# PCIe_ETHERNET.net
KiCad netlist of a schematic drawn in Altium Designer
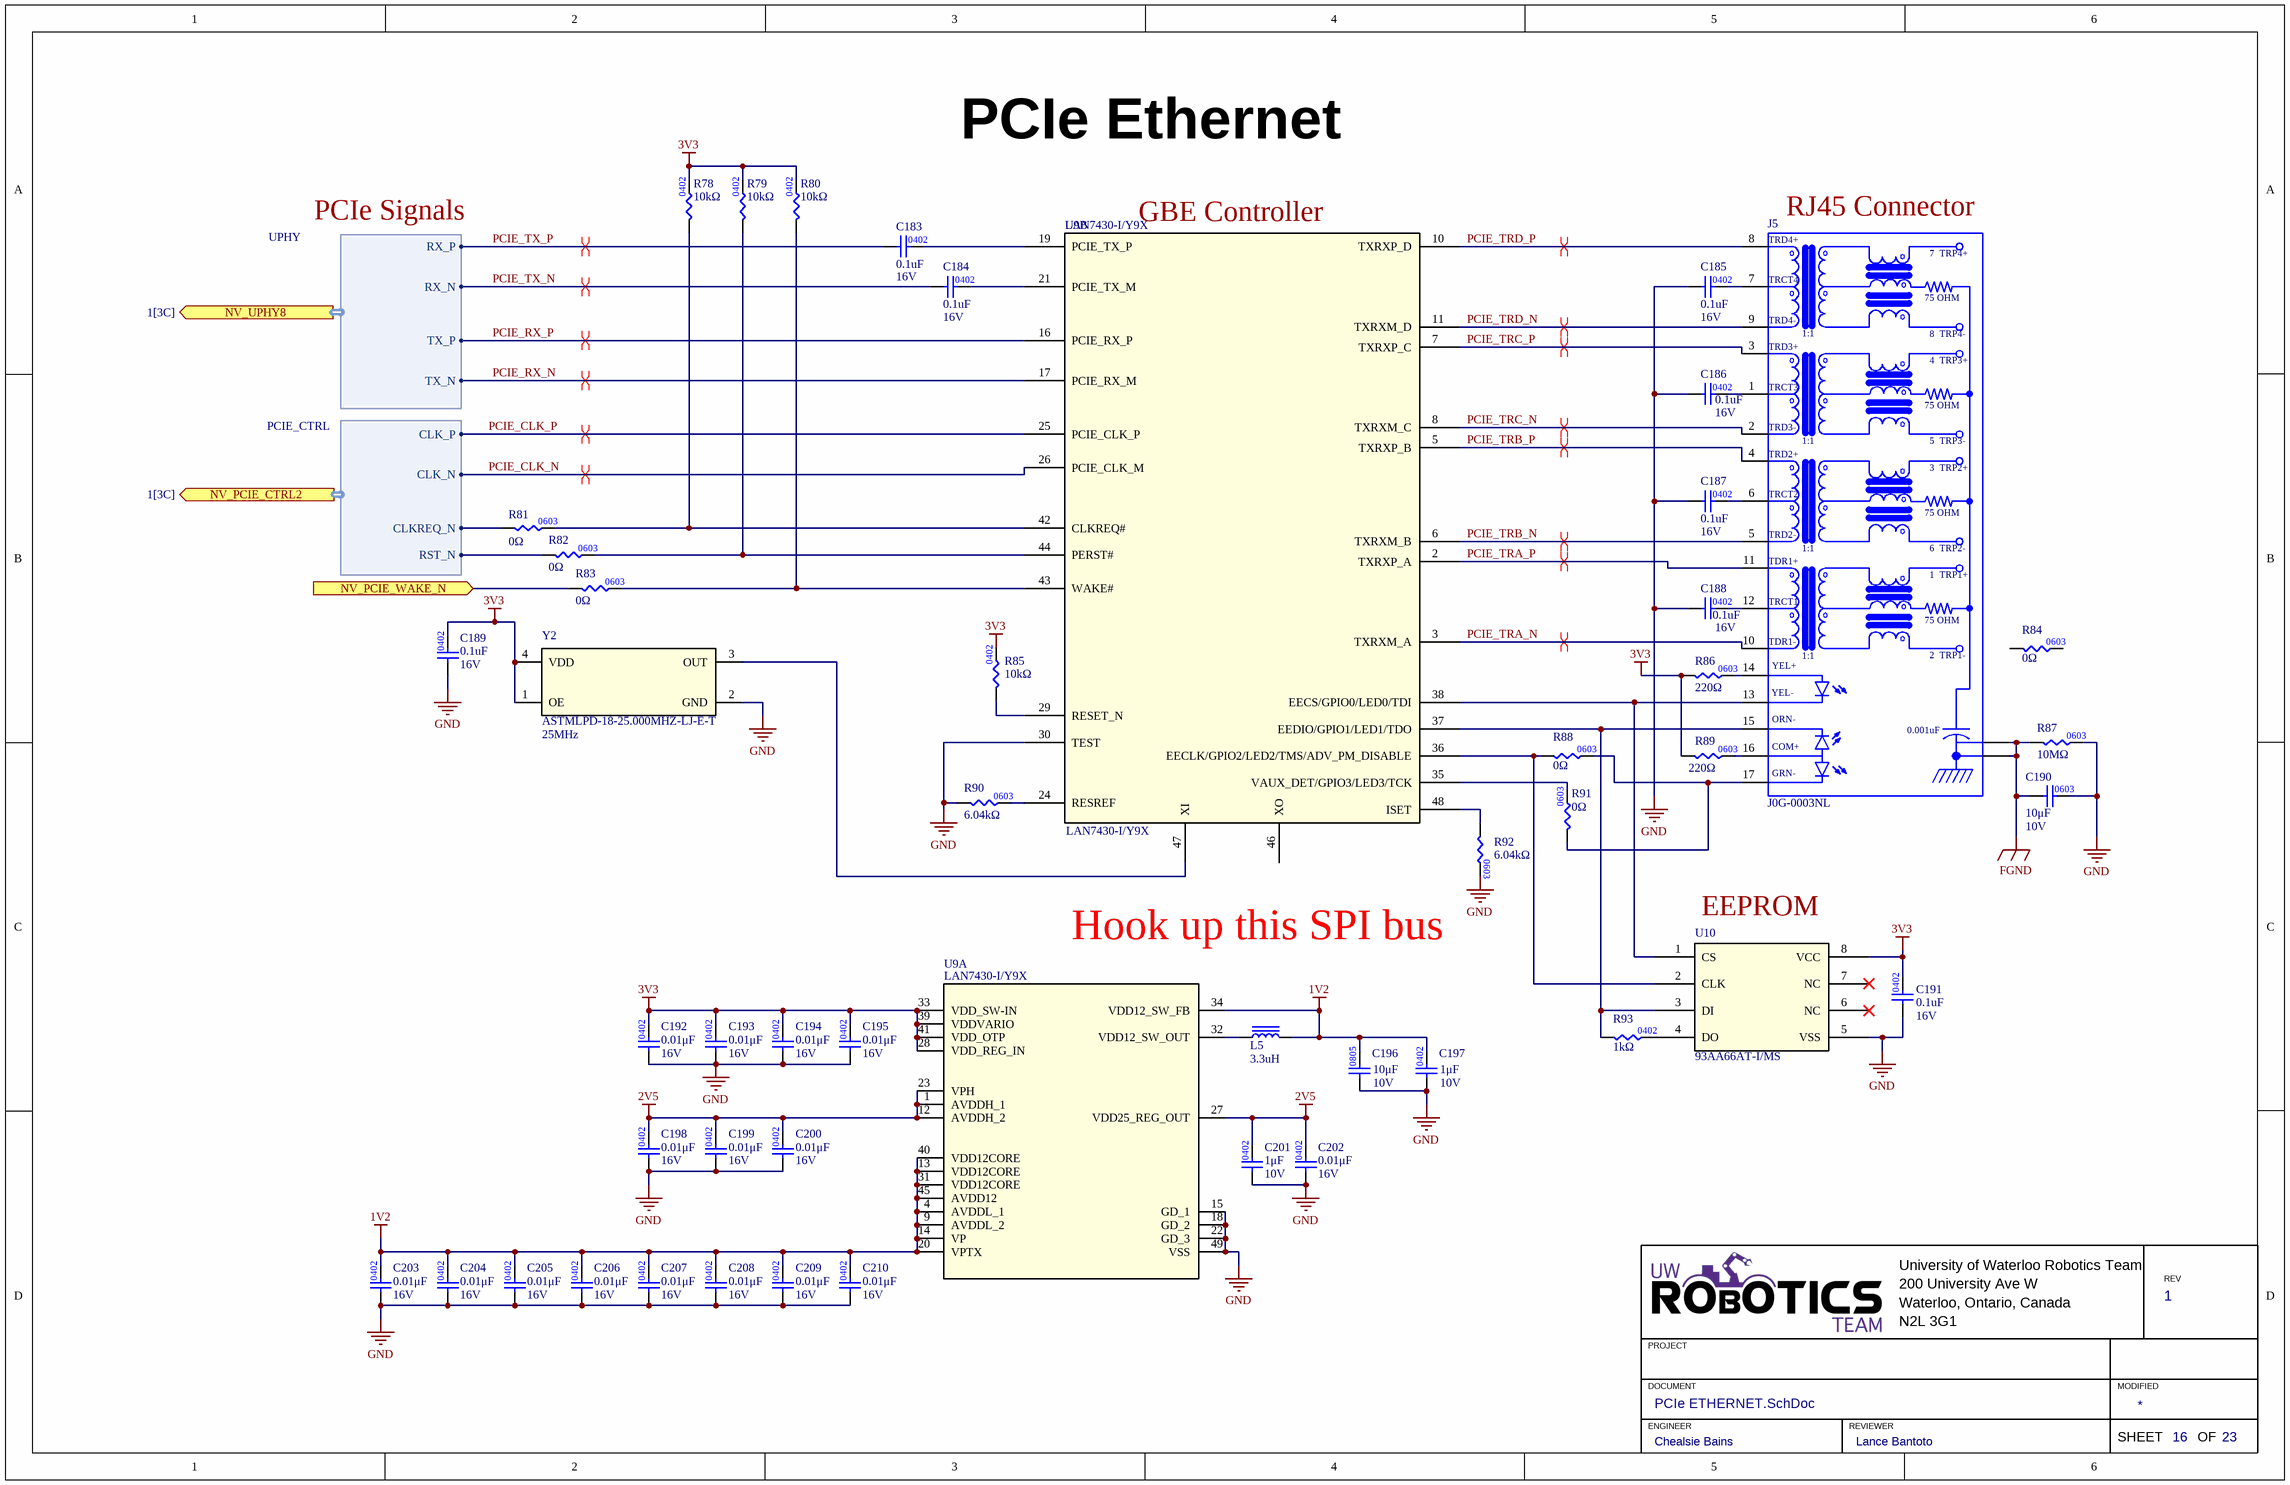
[diagram p0: PCIe ETHERNET.SchDoc]

(export (version "E")
  (design (tool "Eeschema 10.0.6"))
  (components
    (comp (ref "C183")
      (value "CAP_0.1uF_16V_X7R_0402")
      (footprint "CAP0402")
      (description "CAP CER 0.1UF 16V X7R 0402")
      (fields (field (name "CAPACITANCE") "0.1uF") (field (name "VOLTAGE RATING") "16V"))
      (libsource (lib "UWRT_Schematic_Library_2020") (part "CAP_0.1uF_16V_X7R_0402"))
    )
    (comp (ref "C184")
      (value "CAP_0.1uF_16V_X7R_0402")
      (footprint "CAP0402")
      (description "CAP CER 0.1UF 16V X7R 0402")
      (fields (field (name "CAPACITANCE") "0.1uF") (field (name "VOLTAGE RATING") "16V"))
      (libsource (lib "UWRT_Schematic_Library_2020") (part "CAP_0.1uF_16V_X7R_0402"))
    )
    (comp (ref "C185")
      (value "CAP_0.1uF_16V_X7R_0402")
      (footprint "CAP0402")
      (description "CAP CER 0.1UF 16V X7R 0402")
      (fields (field (name "CAPACITANCE") "0.1uF") (field (name "VOLTAGE RATING") "16V"))
      (libsource (lib "UWRT_Schematic_Library_2020") (part "CAP_0.1uF_16V_X7R_0402"))
    )
    (comp (ref "C186")
      (value "CAP_0.1uF_16V_X7R_0402")
      (footprint "CAP0402")
      (description "CAP CER 0.1UF 16V X7R 0402")
      (fields (field (name "CAPACITANCE") "0.1uF") (field (name "VOLTAGE RATING") "16V"))
      (libsource (lib "UWRT_Schematic_Library_2020") (part "CAP_0.1uF_16V_X7R_0402"))
    )
    (comp (ref "C187")
      (value "CAP_0.1uF_16V_X7R_0402")
      (footprint "CAP0402")
      (description "CAP CER 0.1UF 16V X7R 0402")
      (fields (field (name "CAPACITANCE") "0.1uF") (field (name "VOLTAGE RATING") "16V"))
      (libsource (lib "UWRT_Schematic_Library_2020") (part "CAP_0.1uF_16V_X7R_0402"))
    )
    (comp (ref "C188")
      (value "CAP_0.1uF_16V_X7R_0402")
      (footprint "CAP0402")
      (description "CAP CER 0.1UF 16V X7R 0402")
      (fields (field (name "CAPACITANCE") "0.1uF") (field (name "VOLTAGE RATING") "16V"))
      (libsource (lib "UWRT_Schematic_Library_2020") (part "CAP_0.1uF_16V_X7R_0402"))
    )
    (comp (ref "C189")
      (value "CAP_0.1uF_16V_X7R_0402")
      (footprint "CAP0402")
      (description "CAP CER 0.1UF 16V X7R 0402")
      (fields (field (name "CAPACITANCE") "0.1uF") (field (name "VOLTAGE RATING") "16V"))
      (libsource (lib "UWRT_Schematic_Library_2020") (part "CAP_0.1uF_16V_X7R_0402"))
    )
    (comp (ref "C190")
      (value "10μF")
      (footprint "CAP0603")
      (description "CAP CER 10UF 10V X5R 0603")
      (fields (field (name "VOLTAGE RATING") "10V") (field (name "Comment") "CAP_10uF_10V_0603"))
      (libsource (lib "UWRT_Schematic_Library_2020") (part "CAP_10uF_10V_0603"))
    )
    (comp (ref "C191")
      (value "CAP_0.1uF_16V_X7R_0402")
      (footprint "CAP0402")
      (description "CAP CER 0.1UF 16V X7R 0402")
      (fields (field (name "CAPACITANCE") "0.1uF") (field (name "VOLTAGE RATING") "16V"))
      (libsource (lib "UWRT_Schematic_Library_2020") (part "CAP_0.1uF_16V_X7R_0402"))
    )
    (comp (ref "C192")
      (value "CAP_0.01uF_16V_X7R_0402")
      (footprint "CAP0402")
      (description "CAP CER 0.01uF 16V X7R 0402")
      (fields
        (field (name "MANUFACTURER") "KEMET")
        (field (name "MANUFACTURER PART NUMBER") "C0402C103J4RACTU")
        (field (name "CAPACITANCE") "0.01μF")
        (field (name "VOLTAGE RATING") "16V")
      )
      (libsource (lib "UWRT_Schematic_Library_2020") (part "CAP_0.01uF_16V_X7R_0402"))
    )
    (comp (ref "C193")
      (value "CAP_0.01uF_16V_X7R_0402")
      (footprint "CAP0402")
      (description "CAP CER 0.01uF 16V X7R 0402")
      (fields
        (field (name "MANUFACTURER") "KEMET")
        (field (name "MANUFACTURER PART NUMBER") "C0402C103J4RACTU")
        (field (name "CAPACITANCE") "0.01μF")
        (field (name "VOLTAGE RATING") "16V")
      )
      (libsource (lib "UWRT_Schematic_Library_2020") (part "CAP_0.01uF_16V_X7R_0402"))
    )
    (comp (ref "C194")
      (value "CAP_0.01uF_16V_X7R_0402")
      (footprint "CAP0402")
      (description "CAP CER 0.01uF 16V X7R 0402")
      (fields
        (field (name "MANUFACTURER") "KEMET")
        (field (name "MANUFACTURER PART NUMBER") "C0402C103J4RACTU")
        (field (name "CAPACITANCE") "0.01μF")
        (field (name "VOLTAGE RATING") "16V")
      )
      (libsource (lib "UWRT_Schematic_Library_2020") (part "CAP_0.01uF_16V_X7R_0402"))
    )
    (comp (ref "C195")
      (value "CAP_0.01uF_16V_X7R_0402")
      (footprint "CAP0402")
      (description "CAP CER 0.01uF 16V X7R 0402")
      (fields
        (field (name "MANUFACTURER") "KEMET")
        (field (name "MANUFACTURER PART NUMBER") "C0402C103J4RACTU")
        (field (name "CAPACITANCE") "0.01μF")
        (field (name "VOLTAGE RATING") "16V")
      )
      (libsource (lib "UWRT_Schematic_Library_2020") (part "CAP_0.01uF_16V_X7R_0402"))
    )
    (comp (ref "C196")
      (value "10μF")
      (footprint "CAP0805")
      (description "CAP CER 10UF 10V X6S 0805")
      (fields (field (name "VOLTAGE RATING") "10V") (field (name "Comment") "CAP_10UF_10V_X6S_0805"))
      (libsource (lib "UWRT_Schematic_Library_2020") (part "CAP_10UF_10V_X6S_0805"))
    )
    (comp (ref "C197")
      (value "CAP_1UF_10V_0402_X5R")
      (footprint "CAP0402")
      (description "CAP CER 1UF 10V X5R 0402")
      (fields
        (field (name "MANUFACTURER") "Kyocera AVX")
        (field (name "MANUFACTURER PART NUMBER") "0402ZD105MAT2A")
        (field (name "CAPACITANCE") "1μF")
        (field (name "RATED DC VOLTAGE (URDC)") "10V")
      )
      (libsource (lib "UWRT_Schematic_Library_2020") (part "CAP_1UF_10V_0402_X5R"))
    )
    (comp (ref "C198")
      (value "CAP_0.01uF_16V_X7R_0402")
      (footprint "CAP0402")
      (description "CAP CER 0.01uF 16V X7R 0402")
      (fields
        (field (name "MANUFACTURER") "KEMET")
        (field (name "MANUFACTURER PART NUMBER") "C0402C103J4RACTU")
        (field (name "CAPACITANCE") "0.01μF")
        (field (name "VOLTAGE RATING") "16V")
      )
      (libsource (lib "UWRT_Schematic_Library_2020") (part "CAP_0.01uF_16V_X7R_0402"))
    )
    (comp (ref "C199")
      (value "CAP_0.01uF_16V_X7R_0402")
      (footprint "CAP0402")
      (description "CAP CER 0.01uF 16V X7R 0402")
      (fields
        (field (name "MANUFACTURER") "KEMET")
        (field (name "MANUFACTURER PART NUMBER") "C0402C103J4RACTU")
        (field (name "CAPACITANCE") "0.01μF")
        (field (name "VOLTAGE RATING") "16V")
      )
      (libsource (lib "UWRT_Schematic_Library_2020") (part "CAP_0.01uF_16V_X7R_0402"))
    )
    (comp (ref "C200")
      (value "CAP_0.01uF_16V_X7R_0402")
      (footprint "CAP0402")
      (description "CAP CER 0.01uF 16V X7R 0402")
      (fields
        (field (name "MANUFACTURER") "KEMET")
        (field (name "MANUFACTURER PART NUMBER") "C0402C103J4RACTU")
        (field (name "CAPACITANCE") "0.01μF")
        (field (name "VOLTAGE RATING") "16V")
      )
      (libsource (lib "UWRT_Schematic_Library_2020") (part "CAP_0.01uF_16V_X7R_0402"))
    )
    (comp (ref "C201")
      (value "CAP_1UF_10V_0402_X5R")
      (footprint "CAP0402")
      (description "CAP CER 1UF 10V X5R 0402")
      (fields
        (field (name "MANUFACTURER") "Kyocera AVX")
        (field (name "MANUFACTURER PART NUMBER") "0402ZD105MAT2A")
        (field (name "CAPACITANCE") "1μF")
        (field (name "RATED DC VOLTAGE (URDC)") "10V")
      )
      (libsource (lib "UWRT_Schematic_Library_2020") (part "CAP_1UF_10V_0402_X5R"))
    )
    (comp (ref "C202")
      (value "CAP_0.01uF_16V_X7R_0402")
      (footprint "CAP0402")
      (description "CAP CER 0.01uF 16V X7R 0402")
      (fields
        (field (name "MANUFACTURER") "KEMET")
        (field (name "MANUFACTURER PART NUMBER") "C0402C103J4RACTU")
        (field (name "CAPACITANCE") "0.01μF")
        (field (name "VOLTAGE RATING") "16V")
      )
      (libsource (lib "UWRT_Schematic_Library_2020") (part "CAP_0.01uF_16V_X7R_0402"))
    )
    (comp (ref "C203")
      (value "CAP_0.01uF_16V_X7R_0402")
      (footprint "CAP0402")
      (description "CAP CER 0.01uF 16V X7R 0402")
      (fields
        (field (name "MANUFACTURER") "KEMET")
        (field (name "MANUFACTURER PART NUMBER") "C0402C103J4RACTU")
        (field (name "CAPACITANCE") "0.01μF")
        (field (name "VOLTAGE RATING") "16V")
      )
      (libsource (lib "UWRT_Schematic_Library_2020") (part "CAP_0.01uF_16V_X7R_0402"))
    )
    (comp (ref "C204")
      (value "CAP_0.01uF_16V_X7R_0402")
      (footprint "CAP0402")
      (description "CAP CER 0.01uF 16V X7R 0402")
      (fields
        (field (name "MANUFACTURER") "KEMET")
        (field (name "MANUFACTURER PART NUMBER") "C0402C103J4RACTU")
        (field (name "CAPACITANCE") "0.01μF")
        (field (name "VOLTAGE RATING") "16V")
      )
      (libsource (lib "UWRT_Schematic_Library_2020") (part "CAP_0.01uF_16V_X7R_0402"))
    )
    (comp (ref "C205")
      (value "CAP_0.01uF_16V_X7R_0402")
      (footprint "CAP0402")
      (description "CAP CER 0.01uF 16V X7R 0402")
      (fields
        (field (name "MANUFACTURER") "KEMET")
        (field (name "MANUFACTURER PART NUMBER") "C0402C103J4RACTU")
        (field (name "CAPACITANCE") "0.01μF")
        (field (name "VOLTAGE RATING") "16V")
      )
      (libsource (lib "UWRT_Schematic_Library_2020") (part "CAP_0.01uF_16V_X7R_0402"))
    )
    (comp (ref "C206")
      (value "CAP_0.01uF_16V_X7R_0402")
      (footprint "CAP0402")
      (description "CAP CER 0.01uF 16V X7R 0402")
      (fields
        (field (name "MANUFACTURER") "KEMET")
        (field (name "MANUFACTURER PART NUMBER") "C0402C103J4RACTU")
        (field (name "CAPACITANCE") "0.01μF")
        (field (name "VOLTAGE RATING") "16V")
      )
      (libsource (lib "UWRT_Schematic_Library_2020") (part "CAP_0.01uF_16V_X7R_0402"))
    )
    (comp (ref "C207")
      (value "CAP_0.01uF_16V_X7R_0402")
      (footprint "CAP0402")
      (description "CAP CER 0.01uF 16V X7R 0402")
      (fields
        (field (name "MANUFACTURER") "KEMET")
        (field (name "MANUFACTURER PART NUMBER") "C0402C103J4RACTU")
        (field (name "CAPACITANCE") "0.01μF")
        (field (name "VOLTAGE RATING") "16V")
      )
      (libsource (lib "UWRT_Schematic_Library_2020") (part "CAP_0.01uF_16V_X7R_0402"))
    )
    (comp (ref "C208")
      (value "CAP_0.01uF_16V_X7R_0402")
      (footprint "CAP0402")
      (description "CAP CER 0.01uF 16V X7R 0402")
      (fields
        (field (name "MANUFACTURER") "KEMET")
        (field (name "MANUFACTURER PART NUMBER") "C0402C103J4RACTU")
        (field (name "CAPACITANCE") "0.01μF")
        (field (name "VOLTAGE RATING") "16V")
      )
      (libsource (lib "UWRT_Schematic_Library_2020") (part "CAP_0.01uF_16V_X7R_0402"))
    )
    (comp (ref "C209")
      (value "CAP_0.01uF_16V_X7R_0402")
      (footprint "CAP0402")
      (description "CAP CER 0.01uF 16V X7R 0402")
      (fields
        (field (name "MANUFACTURER") "KEMET")
        (field (name "MANUFACTURER PART NUMBER") "C0402C103J4RACTU")
        (field (name "CAPACITANCE") "0.01μF")
        (field (name "VOLTAGE RATING") "16V")
      )
      (libsource (lib "UWRT_Schematic_Library_2020") (part "CAP_0.01uF_16V_X7R_0402"))
    )
    (comp (ref "C210")
      (value "CAP_0.01uF_16V_X7R_0402")
      (footprint "CAP0402")
      (description "CAP CER 0.01uF 16V X7R 0402")
      (fields
        (field (name "MANUFACTURER") "KEMET")
        (field (name "MANUFACTURER PART NUMBER") "C0402C103J4RACTU")
        (field (name "CAPACITANCE") "0.01μF")
        (field (name "VOLTAGE RATING") "16V")
      )
      (libsource (lib "UWRT_Schematic_Library_2020") (part "CAP_0.01uF_16V_X7R_0402"))
    )
    (comp (ref "J5")
      (value "J0G-0003NL")
      (footprint "PULSE_J0G-0003NL")
      (description "1 Port RJ45 Magjack Connector Through Hole 10/100/1000 Base-T, AutoMDIX")
      (fields (field (name "DIGI-KEY_PART_NUMBER") "553-1852-ND") (field (name "MF") "Pulse Electronics"))
      (libsource (lib "UWRT_Schematic_Library_2020") (part "J0G-0003NL"))
    )
    (comp (ref "L5")
      (value "IND_3.3uH")
      (footprint "IND_BOURNS_SRN6045")
      (description "FIXED INDUCTOR 3.3UH SMD")
      (fields (field (name "INDUCTANCE") "3.3uH"))
      (libsource (lib "UWRT_Schematic_Library_2020") (part "IND_3.3uH"))
    )
    (comp (ref "R78")
      (value "RES_10kΩ_0402")
      (footprint "RES0805")
      (description "Fixed Resistor, Thin Film, 0.1W, 10000ohm, 50V, 0.1% +/-Tol, 25ppm/Cel, Surface Mount, 0402")
      (fields
        (field (name "MANUFACTURER") "Stackpole Electronics")
        (field (name "MANUFACTURER PART NUMBER") "RNCF0402BTE10K0")
        (field (name "RESISTANCE") "10kΩ")
      )
      (libsource (lib "UWRT_Schematic_Library_2020") (part "RES_10kΩ_0402"))
    )
    (comp (ref "R79")
      (value "RES_10kΩ_0402")
      (footprint "RES0805")
      (description "Fixed Resistor, Thin Film, 0.1W, 10000ohm, 50V, 0.1% +/-Tol, 25ppm/Cel, Surface Mount, 0402")
      (fields
        (field (name "MANUFACTURER") "Stackpole Electronics")
        (field (name "MANUFACTURER PART NUMBER") "RNCF0402BTE10K0")
        (field (name "RESISTANCE") "10kΩ")
      )
      (libsource (lib "UWRT_Schematic_Library_2020") (part "RES_10kΩ_0402"))
    )
    (comp (ref "R80")
      (value "RES_10kΩ_0402")
      (footprint "RES0805")
      (description "Fixed Resistor, Thin Film, 0.1W, 10000ohm, 50V, 0.1% +/-Tol, 25ppm/Cel, Surface Mount, 0402")
      (fields
        (field (name "MANUFACTURER") "Stackpole Electronics")
        (field (name "MANUFACTURER PART NUMBER") "RNCF0402BTE10K0")
        (field (name "RESISTANCE") "10kΩ")
      )
      (libsource (lib "UWRT_Schematic_Library_2020") (part "RES_10kΩ_0402"))
    )
    (comp (ref "R81")
      (value "0Ω")
      (footprint "RES0603")
      (description "RES 0 OHM JUMPER 1/10W 0603")
      (fields (field (name "Comment") "RES_0Ω_0603"))
      (libsource (lib "UWRT_Schematic_Library_2020") (part "RES_0Ω_0603"))
    )
    (comp (ref "R82")
      (value "0Ω")
      (footprint "RES0603")
      (description "RES 0 OHM JUMPER 1/10W 0603")
      (fields (field (name "Comment") "RES_0Ω_0603"))
      (libsource (lib "UWRT_Schematic_Library_2020") (part "RES_0Ω_0603"))
    )
    (comp (ref "R83")
      (value "0Ω")
      (footprint "RES0603")
      (description "RES 0 OHM JUMPER 1/10W 0603")
      (fields (field (name "Comment") "RES_0Ω_0603"))
      (libsource (lib "UWRT_Schematic_Library_2020") (part "RES_0Ω_0603"))
    )
    (comp (ref "R84")
      (value "0Ω")
      (footprint "RES0603")
      (description "RES 0 OHM JUMPER 1/10W 0603")
      (fields (field (name "Comment") "RES_0Ω_0603"))
      (libsource (lib "UWRT_Schematic_Library_2020") (part "RES_0Ω_0603"))
    )
    (comp (ref "R85")
      (value "RES_10kΩ_0402")
      (footprint "RES0805")
      (description "Fixed Resistor, Thin Film, 0.1W, 10000ohm, 50V, 0.1% +/-Tol, 25ppm/Cel, Surface Mount, 0402")
      (fields
        (field (name "MANUFACTURER") "Stackpole Electronics")
        (field (name "MANUFACTURER PART NUMBER") "RNCF0402BTE10K0")
        (field (name "RESISTANCE") "10kΩ")
      )
      (libsource (lib "UWRT_Schematic_Library_2020") (part "RES_10kΩ_0402"))
    )
    (comp (ref "R86")
      (value "220Ω")
      (footprint "RES0603")
      (description "RES 220 OHM 5% 1/10W 0603")
      (fields (field (name "Comment") "RES_220Ω_0603"))
      (libsource (lib "UWRT_Schematic_Library_2020") (part "RES_220Ω_0603_5%"))
    )
    (comp (ref "R87")
      (value "10MΩ")
      (footprint "RES0603")
      (description "RES 10M OHM 5% 1/10W 0603")
      (fields (field (name "Comment") "RES_10MΩ_0603"))
      (libsource (lib "UWRT_Schematic_Library_2020") (part "RES_10MΩ_0603_5%"))
    )
    (comp (ref "R88")
      (value "0Ω")
      (footprint "RES0603")
      (description "RES 0 OHM JUMPER 1/10W 0603")
      (fields (field (name "Comment") "RES_0Ω_0603"))
      (libsource (lib "UWRT_Schematic_Library_2020") (part "RES_0Ω_0603"))
    )
    (comp (ref "R89")
      (value "220Ω")
      (footprint "RES0603")
      (description "RES 220 OHM 5% 1/10W 0603")
      (fields (field (name "Comment") "RES_220Ω_0603"))
      (libsource (lib "UWRT_Schematic_Library_2020") (part "RES_220Ω_0603_5%"))
    )
    (comp (ref "R90")
      (value "6.04kΩ")
      (footprint "RES0603")
      (description "RES 6.04K OHM 1% 1/10W 0603")
      (fields (field (name "Comment") "RES_6.04kΩ_0603_1%"))
      (libsource (lib "UWRT_Schematic_Library_2020") (part "RES_6.04kΩ_0603_1%"))
    )
    (comp (ref "R91")
      (value "0Ω")
      (footprint "RES0603")
      (description "RES 0 OHM JUMPER 1/10W 0603")
      (fields (field (name "Comment") "RES_0Ω_0603"))
      (libsource (lib "UWRT_Schematic_Library_2020") (part "RES_0Ω_0603"))
    )
    (comp (ref "R92")
      (value "6.04kΩ")
      (footprint "RES0603")
      (description "RES 6.04K OHM 1% 1/10W 0603")
      (fields (field (name "Comment") "RES_6.04kΩ_0603_1%"))
      (libsource (lib "UWRT_Schematic_Library_2020") (part "RES_6.04kΩ_0603_1%"))
    )
    (comp (ref "R93")
      (value "1kΩ")
      (footprint "RES0402")
      (description "RES 1K OHM 1% 1/16W 0402")
      (fields (field (name "TOLERANCE") "1%") (field (name "Comment") "RES_1kΩ_0402_1%"))
      (libsource (lib "UWRT_Schematic_Library_2020") (part "RES_1kΩ_0402_1%"))
    )
    (comp (ref "U9")
      (value "LAN7430-I/Y9X")
      (footprint "LAN7430-I/Y9X-ND")
      (description "IC ETHERNET CNTRLR GPIO 48SQFN")
      (fields (field (name "MANUFACTURER PART NUMBER 1") "LAN7430-I/Y9X"))
      (libsource (lib "UWRT_Schematic_Library_2020") (part "LAN7430-I/Y9X"))
    )
    (comp (ref "U10")
      (value "93AA66AT-I/MS")
      (footprint "SOP65P490X110-8N")
      (description "IC EEPROM 4KBIT SPI 2MHZ 8MSOP")
      (fields (field (name "MANUFACTURER PART NUMBER 1") "93AA66AT-I/MS"))
      (libsource (lib "UWRT_Schematic_Library_2020") (part "93AA66AT-I/MS"))
    )
    (comp (ref "Y2")
      (value "25MHz")
      (footprint "ASTMLPE_ABR")
      (description "MEMS OSC XO 25.0000MHZ LVCMOS")
      (fields
        (field (name "MANUFACTURER PART NUMBER 1") "ASTMLPD-18-25.000MHZ-LJ-E-T")
        (field (name "Comment") "ASTMLPD-18-25.000MHZ-LJ-E-T")
      )
      (libsource (lib "UWRT_Schematic_Library_2020") (part "ASTMLPD-18-25.000MHZ-LJ-E-T"))
    )
  )
  (nets
    (net (code "3") (name "/CLKREQ_N") (class "Default")
      (node (ref "R81") (pin "1") (pinfunction "1_1") (pintype "passive"))
    )
    (net (code "4") (name "/NV_PCIE_WAKE_N") (class "Default")
      (node (ref "R83") (pin "1") (pinfunction "1_1") (pintype "passive"))
    )
    (net (code "5") (name "/PCIE_CLK_N") (class "Default")
      (node (ref "U9") (pin "26") (pinfunction "PCIE_CLK_M_26") (pintype "passive"))
    )
    (net (code "6") (name "/PCIE_CLK_P") (class "Default")
      (node (ref "U9") (pin "25") (pinfunction "PCIE_CLK_P_25") (pintype "passive"))
    )
    (net (code "7") (name "/PCIE_RX_N") (class "Default")
      (node (ref "U9") (pin "17") (pinfunction "PCIE_RX_M_17") (pintype "passive"))
    )
    (net (code "8") (name "/PCIE_RX_P") (class "Default")
      (node (ref "U9") (pin "16") (pinfunction "PCIE_RX_P_16") (pintype "passive"))
    )
    (net (code "9") (name "/PCIE_TRA_N") (class "Default")
      (node (ref "J5") (pin "10") (pinfunction "TDR1-_10") (pintype "passive"))
      (node (ref "U9") (pin "3") (pinfunction "TXRXM_A_3") (pintype "passive"))
    )
    (net (code "10") (name "/PCIE_TRA_P") (class "Default")
      (node (ref "J5") (pin "11") (pinfunction "TDR1+_11") (pintype "passive"))
      (node (ref "U9") (pin "2") (pinfunction "TXRXP_A_2") (pintype "passive"))
    )
    (net (code "11") (name "/PCIE_TRB_N") (class "Default")
      (node (ref "J5") (pin "5") (pinfunction "TRD2-_5") (pintype "passive"))
      (node (ref "U9") (pin "6") (pinfunction "TXRXM_B_6") (pintype "passive"))
    )
    (net (code "12") (name "/PCIE_TRB_P") (class "Default")
      (node (ref "J5") (pin "4") (pinfunction "TRD2+_4") (pintype "passive"))
      (node (ref "U9") (pin "5") (pinfunction "TXRXP_B_5") (pintype "passive"))
    )
    (net (code "13") (name "/PCIE_TRC_N") (class "Default")
      (node (ref "J5") (pin "2") (pinfunction "TRD3-_2") (pintype "passive"))
      (node (ref "U9") (pin "8") (pinfunction "TXRXM_C_8") (pintype "passive"))
    )
    (net (code "14") (name "/PCIE_TRC_P") (class "Default")
      (node (ref "J5") (pin "3") (pinfunction "TRD3+_3") (pintype "passive"))
      (node (ref "U9") (pin "7") (pinfunction "TXRXP_C_7") (pintype "passive"))
    )
    (net (code "15") (name "/PCIE_TRD_N") (class "Default")
      (node (ref "J5") (pin "9") (pinfunction "TRD4-_9") (pintype "passive"))
      (node (ref "U9") (pin "11") (pinfunction "TXRXM_D_11") (pintype "passive"))
    )
    (net (code "16") (name "/PCIE_TRD_P") (class "Default")
      (node (ref "J5") (pin "8") (pinfunction "TRD4+_8") (pintype "passive"))
      (node (ref "U9") (pin "10") (pinfunction "TXRXP_D_10") (pintype "passive"))
    )
    (net (code "17") (name "/PCIE_TX_N") (class "Default")
      (node (ref "C184") (pin "1") (pinfunction "1_1") (pintype "passive"))
    )
    (net (code "18") (name "/PCIE_TX_P") (class "Default")
      (node (ref "C183") (pin "1") (pinfunction "1_1") (pintype "passive"))
    )
    (net (code "19") (name "/RST_N") (class "Default")
      (node (ref "R82") (pin "1") (pinfunction "1_1") (pintype "passive"))
    )
    (net (code "22") (name "1V2") (class "Default")
      (node (ref "C196") (pin "2") (pinfunction "2_2") (pintype "passive"))
      (node (ref "C197") (pin "2") (pinfunction "2_2") (pintype "passive"))
      (node (ref "C203") (pin "2") (pinfunction "2_2") (pintype "passive"))
      (node (ref "C204") (pin "2") (pinfunction "2_2") (pintype "passive"))
      (node (ref "C205") (pin "2") (pinfunction "2_2") (pintype "passive"))
      (node (ref "C206") (pin "2") (pinfunction "2_2") (pintype "passive"))
      (node (ref "C207") (pin "2") (pinfunction "2_2") (pintype "passive"))
      (node (ref "C208") (pin "2") (pinfunction "2_2") (pintype "passive"))
      (node (ref "C209") (pin "2") (pinfunction "2_2") (pintype "passive"))
      (node (ref "C210") (pin "2") (pinfunction "2_2") (pintype "passive"))
      (node (ref "L5") (pin "2") (pinfunction "2_2") (pintype "passive"))
      (node (ref "U9") (pin "13") (pinfunction "VDD12CORE_13") (pintype "passive"))
      (node (ref "U9") (pin "14") (pinfunction "VP_14") (pintype "passive"))
      (node (ref "U9") (pin "20") (pinfunction "VPTX_20") (pintype "passive"))
      (node (ref "U9") (pin "31") (pinfunction "VDD12CORE_31") (pintype "passive"))
      (node (ref "U9") (pin "34") (pinfunction "VDD12_SW_FB_34") (pintype "passive"))
      (node (ref "U9") (pin "4") (pinfunction "AVDDL_1_4") (pintype "passive"))
      (node (ref "U9") (pin "40") (pinfunction "VDD12CORE_40") (pintype "passive"))
      (node (ref "U9") (pin "45") (pinfunction "AVDD12_45") (pintype "passive"))
      (node (ref "U9") (pin "9") (pinfunction "AVDDL_2_9") (pintype "passive"))
    )
    (net (code "23") (name "2V5") (class "Default")
      (node (ref "C198") (pin "2") (pinfunction "2_2") (pintype "passive"))
      (node (ref "C199") (pin "2") (pinfunction "2_2") (pintype "passive"))
      (node (ref "C200") (pin "2") (pinfunction "2_2") (pintype "passive"))
      (node (ref "C201") (pin "2") (pinfunction "2_2") (pintype "passive"))
      (node (ref "C202") (pin "2") (pinfunction "2_2") (pintype "passive"))
      (node (ref "U9") (pin "1") (pinfunction "AVDDH_1_1") (pintype "passive"))
      (node (ref "U9") (pin "12") (pinfunction "AVDDH_2_12") (pintype "passive"))
      (node (ref "U9") (pin "23") (pinfunction "VPH_23") (pintype "passive"))
      (node (ref "U9") (pin "27") (pinfunction "VDD25_REG_OUT_27") (pintype "passive"))
    )
    (net (code "24") (name "3V3") (class "Default")
      (node (ref "C189") (pin "2") (pinfunction "2_2") (pintype "passive"))
      (node (ref "C191") (pin "2") (pinfunction "2_2") (pintype "passive"))
      (node (ref "C192") (pin "2") (pinfunction "2_2") (pintype "passive"))
      (node (ref "C193") (pin "2") (pinfunction "2_2") (pintype "passive"))
      (node (ref "C194") (pin "2") (pinfunction "2_2") (pintype "passive"))
      (node (ref "C195") (pin "2") (pinfunction "2_2") (pintype "passive"))
      (node (ref "R78") (pin "2") (pinfunction "2_2") (pintype "passive"))
      (node (ref "R79") (pin "2") (pinfunction "2_2") (pintype "passive"))
      (node (ref "R80") (pin "2") (pinfunction "2_2") (pintype "passive"))
      (node (ref "R85") (pin "2") (pinfunction "2_2") (pintype "passive"))
      (node (ref "R86") (pin "1") (pinfunction "1_1") (pintype "passive"))
      (node (ref "R89") (pin "1") (pinfunction "1_1") (pintype "passive"))
      (node (ref "U10") (pin "8") (pinfunction "VCC_8") (pintype "passive"))
      (node (ref "U9") (pin "28") (pinfunction "VDD_REG_IN_28") (pintype "passive"))
      (node (ref "U9") (pin "33") (pinfunction "VDD_SW-IN_33") (pintype "passive"))
      (node (ref "U9") (pin "39") (pinfunction "VDDVARIO_39") (pintype "passive"))
      (node (ref "U9") (pin "41") (pinfunction "VDD_OTP_41") (pintype "passive"))
      (node (ref "Y2") (pin "1") (pinfunction "OE_1") (pintype "passive"))
      (node (ref "Y2") (pin "4") (pinfunction "VDD_4") (pintype "passive"))
    )
    (net (code "25") (name "FGND") (class "Default")
      (node (ref "C190") (pin "1") (pinfunction "1_1") (pintype "passive"))
      (node (ref "J5") (pin "SH1") (pinfunction "SHIELD_SH1") (pintype "power_in"))
      (node (ref "J5") (pin "SH2") (pinfunction "SHIELD_SH2") (pintype "power_in"))
      (node (ref "R87") (pin "1") (pinfunction "1_1") (pintype "passive"))
    )
    (net (code "26") (name "GND") (class "Default")
      (node (ref "C185") (pin "1") (pinfunction "1_1") (pintype "passive"))
      (node (ref "C186") (pin "1") (pinfunction "1_1") (pintype "passive"))
      (node (ref "C187") (pin "1") (pinfunction "1_1") (pintype "passive"))
      (node (ref "C188") (pin "1") (pinfunction "1_1") (pintype "passive"))
      (node (ref "C189") (pin "1") (pinfunction "1_1") (pintype "passive"))
      (node (ref "C190") (pin "2") (pinfunction "2_2") (pintype "passive"))
      (node (ref "C191") (pin "1") (pinfunction "1_1") (pintype "passive"))
      (node (ref "C192") (pin "1") (pinfunction "1_1") (pintype "passive"))
      (node (ref "C193") (pin "1") (pinfunction "1_1") (pintype "passive"))
      (node (ref "C194") (pin "1") (pinfunction "1_1") (pintype "passive"))
      (node (ref "C195") (pin "1") (pinfunction "1_1") (pintype "passive"))
      (node (ref "C196") (pin "1") (pinfunction "1_1") (pintype "passive"))
      (node (ref "C197") (pin "1") (pinfunction "1_1") (pintype "passive"))
      (node (ref "C198") (pin "1") (pinfunction "1_1") (pintype "passive"))
      (node (ref "C199") (pin "1") (pinfunction "1_1") (pintype "passive"))
      (node (ref "C200") (pin "1") (pinfunction "1_1") (pintype "passive"))
      (node (ref "C201") (pin "1") (pinfunction "1_1") (pintype "passive"))
      (node (ref "C202") (pin "1") (pinfunction "1_1") (pintype "passive"))
      (node (ref "C203") (pin "1") (pinfunction "1_1") (pintype "passive"))
      (node (ref "C204") (pin "1") (pinfunction "1_1") (pintype "passive"))
      (node (ref "C205") (pin "1") (pinfunction "1_1") (pintype "passive"))
      (node (ref "C206") (pin "1") (pinfunction "1_1") (pintype "passive"))
      (node (ref "C207") (pin "1") (pinfunction "1_1") (pintype "passive"))
      (node (ref "C208") (pin "1") (pinfunction "1_1") (pintype "passive"))
      (node (ref "C209") (pin "1") (pinfunction "1_1") (pintype "passive"))
      (node (ref "C210") (pin "1") (pinfunction "1_1") (pintype "passive"))
      (node (ref "R87") (pin "2") (pinfunction "2_2") (pintype "passive"))
      (node (ref "R90") (pin "1") (pinfunction "1_1") (pintype "passive"))
      (node (ref "R92") (pin "2") (pinfunction "2_2") (pintype "passive"))
      (node (ref "U10") (pin "5") (pinfunction "VSS_5") (pintype "passive"))
      (node (ref "U9") (pin "15") (pinfunction "GD_1_15") (pintype "passive"))
      (node (ref "U9") (pin "18") (pinfunction "GD_2_18") (pintype "passive"))
      (node (ref "U9") (pin "22") (pinfunction "GD_3_22") (pintype "passive"))
      (node (ref "U9") (pin "30") (pinfunction "TEST_30") (pintype "passive"))
      (node (ref "U9") (pin "49") (pinfunction "VSS_49") (pintype "passive"))
      (node (ref "Y2") (pin "2") (pinfunction "GND_2") (pintype "passive"))
    )
    (net (code "27") (name "Net-(J5-COM+)") (class "Default")
      (node (ref "J5") (pin "16") (pinfunction "COM+_16") (pintype "passive"))
      (node (ref "R89") (pin "2") (pinfunction "2_2") (pintype "passive"))
    )
    (net (code "28") (name "Net-(J5-GRN-)") (class "Default")
      (node (ref "J5") (pin "17") (pinfunction "GRN-_17") (pintype "passive"))
      (node (ref "R88") (pin "2") (pinfunction "2_2") (pintype "passive"))
      (node (ref "R91") (pin "1") (pinfunction "1_1") (pintype "passive"))
    )
    (net (code "29") (name "Net-(J5-ORN-)") (class "Default")
      (node (ref "J5") (pin "15") (pinfunction "ORN-_15") (pintype "passive"))
      (node (ref "R93") (pin "1") (pinfunction "1_1") (pintype "passive"))
      (node (ref "U10") (pin "3") (pinfunction "DI_3") (pintype "passive"))
      (node (ref "U9") (pin "37") (pinfunction "EEDIO/GPIO1/LED1/TDO_37") (pintype "passive"))
    )
    (net (code "30") (name "Net-(J5-TRCT1)") (class "Default")
      (node (ref "C188") (pin "2") (pinfunction "2_2") (pintype "passive"))
      (node (ref "J5") (pin "12") (pinfunction "TRCT1_12") (pintype "passive"))
    )
    (net (code "31") (name "Net-(J5-TRCT2)") (class "Default")
      (node (ref "C187") (pin "2") (pinfunction "2_2") (pintype "passive"))
      (node (ref "J5") (pin "6") (pinfunction "TRCT2_6") (pintype "passive"))
    )
    (net (code "32") (name "Net-(J5-TRCT3)") (class "Default")
      (node (ref "C186") (pin "2") (pinfunction "2_2") (pintype "passive"))
      (node (ref "J5") (pin "1") (pinfunction "TRCT3_1") (pintype "passive"))
    )
    (net (code "33") (name "Net-(J5-TRCT4)") (class "Default")
      (node (ref "C185") (pin "2") (pinfunction "2_2") (pintype "passive"))
      (node (ref "J5") (pin "7") (pinfunction "TRCT4_7") (pintype "passive"))
    )
    (net (code "34") (name "Net-(J5-YEL+)") (class "Default")
      (node (ref "J5") (pin "14") (pinfunction "YEL+_14") (pintype "passive"))
      (node (ref "R86") (pin "2") (pinfunction "2_2") (pintype "passive"))
    )
    (net (code "35") (name "Net-(J5-YEL-)") (class "Default")
      (node (ref "J5") (pin "13") (pinfunction "YEL-_13") (pintype "passive"))
      (node (ref "U10") (pin "1") (pinfunction "CS_1") (pintype "passive"))
      (node (ref "U9") (pin "38") (pinfunction "EECS/GPIO0/LED0/TDI_38") (pintype "passive"))
    )
    (net (code "36") (name "Net-(U9A-VDD12_SW_OUT)") (class "Default")
      (node (ref "L5") (pin "1") (pinfunction "1_1") (pintype "passive"))
      (node (ref "U9") (pin "32") (pinfunction "VDD12_SW_OUT_32") (pintype "passive"))
    )
    (net (code "37") (name "Net-(U9B-CLKREQ#)") (class "Default")
      (node (ref "R78") (pin "1") (pinfunction "1_1") (pintype "passive"))
      (node (ref "R81") (pin "2") (pinfunction "2_2") (pintype "passive"))
      (node (ref "U9") (pin "42") (pinfunction "CLKREQ#_42") (pintype "passive"))
    )
    (net (code "38") (name "Net-(U9B-ISET)") (class "Default")
      (node (ref "R92") (pin "1") (pinfunction "1_1") (pintype "passive"))
      (node (ref "U9") (pin "48") (pinfunction "ISET_48") (pintype "passive"))
    )
    (net (code "39") (name "Net-(U9B-PCIE_TX_M)") (class "Default")
      (node (ref "C184") (pin "2") (pinfunction "2_2") (pintype "passive"))
      (node (ref "U9") (pin "21") (pinfunction "PCIE_TX_M_21") (pintype "passive"))
    )
    (net (code "40") (name "Net-(U9B-PCIE_TX_P)") (class "Default")
      (node (ref "C183") (pin "2") (pinfunction "2_2") (pintype "passive"))
      (node (ref "U9") (pin "19") (pinfunction "PCIE_TX_P_19") (pintype "passive"))
    )
    (net (code "41") (name "Net-(U9B-PERST#)") (class "Default")
      (node (ref "R79") (pin "1") (pinfunction "1_1") (pintype "passive"))
      (node (ref "R82") (pin "2") (pinfunction "2_2") (pintype "passive"))
      (node (ref "U9") (pin "44") (pinfunction "PERST#_44") (pintype "passive"))
    )
    (net (code "42") (name "Net-(U9B-RESET_N)") (class "Default")
      (node (ref "R85") (pin "1") (pinfunction "1_1") (pintype "passive"))
      (node (ref "U9") (pin "29") (pinfunction "RESET_N_29") (pintype "passive"))
    )
    (net (code "43") (name "Net-(U9B-RESREF)") (class "Default")
      (node (ref "R90") (pin "2") (pinfunction "2_2") (pintype "passive"))
      (node (ref "U9") (pin "24") (pinfunction "RESREF_24") (pintype "passive"))
    )
    (net (code "44") (name "Net-(U9B-VAUX_DET{slash}GPIO3{slash}LED3{slash}TCK)") (class "Default")
      (node (ref "R91") (pin "2") (pinfunction "2_2") (pintype "passive"))
      (node (ref "U9") (pin "35") (pinfunction "VAUX_DET/GPIO3/LED3/TCK_35") (pintype "passive"))
    )
    (net (code "45") (name "Net-(U9B-WAKE#)") (class "Default")
      (node (ref "R80") (pin "1") (pinfunction "1_1") (pintype "passive"))
      (node (ref "R83") (pin "2") (pinfunction "2_2") (pintype "passive"))
      (node (ref "U9") (pin "43") (pinfunction "WAKE#_43") (pintype "passive"))
    )
    (net (code "46") (name "Net-(U9B-XI)") (class "Default")
      (node (ref "U9") (pin "47") (pinfunction "XI_47") (pintype "passive"))
      (node (ref "Y2") (pin "3") (pinfunction "OUT_3") (pintype "passive"))
    )
    (net (code "47") (name "Net-(U10-CLK)") (class "Default")
      (node (ref "R88") (pin "1") (pinfunction "1_1") (pintype "passive"))
      (node (ref "U10") (pin "2") (pinfunction "CLK_2") (pintype "passive"))
      (node (ref "U9") (pin "36") (pinfunction "EECLK/GPIO2/LED2/TMS/ADV_PM_DISABLE_36") (pintype "passive"))
    )
    (net (code "48") (name "Net-(U10-DO)") (class "Default")
      (node (ref "R93") (pin "2") (pinfunction "2_2") (pintype "passive"))
      (node (ref "U10") (pin "4") (pinfunction "DO_4") (pintype "passive"))
    )
    (net (code "49") (name "unconnected-(R84-Pad1)") (class "Default")
      (node (ref "R84") (pin "1") (pinfunction "1_1") (pintype "passive"))
    )
    (net (code "50") (name "unconnected-(R84-Pad2)") (class "Default")
      (node (ref "R84") (pin "2") (pinfunction "2_2") (pintype "passive"))
    )
    (net (code "51") (name "unconnected-(U9B-XO-Pad46)") (class "Default")
      (node (ref "U9") (pin "46") (pinfunction "XO_46") (pintype "passive"))
    )
    (net (code "52") (name "unconnected-(U10-NC-Pad6)") (class "Default")
      (node (ref "U10") (pin "6") (pinfunction "NC_6") (pintype "passive+no_connect"))
    )
    (net (code "53") (name "unconnected-(U10-NC-Pad7)") (class "Default")
      (node (ref "U10") (pin "7") (pinfunction "NC_7") (pintype "passive+no_connect"))
    )
  )
)
